# USBhub.net
KiCad netlist of a schematic drawn in Altium Designer
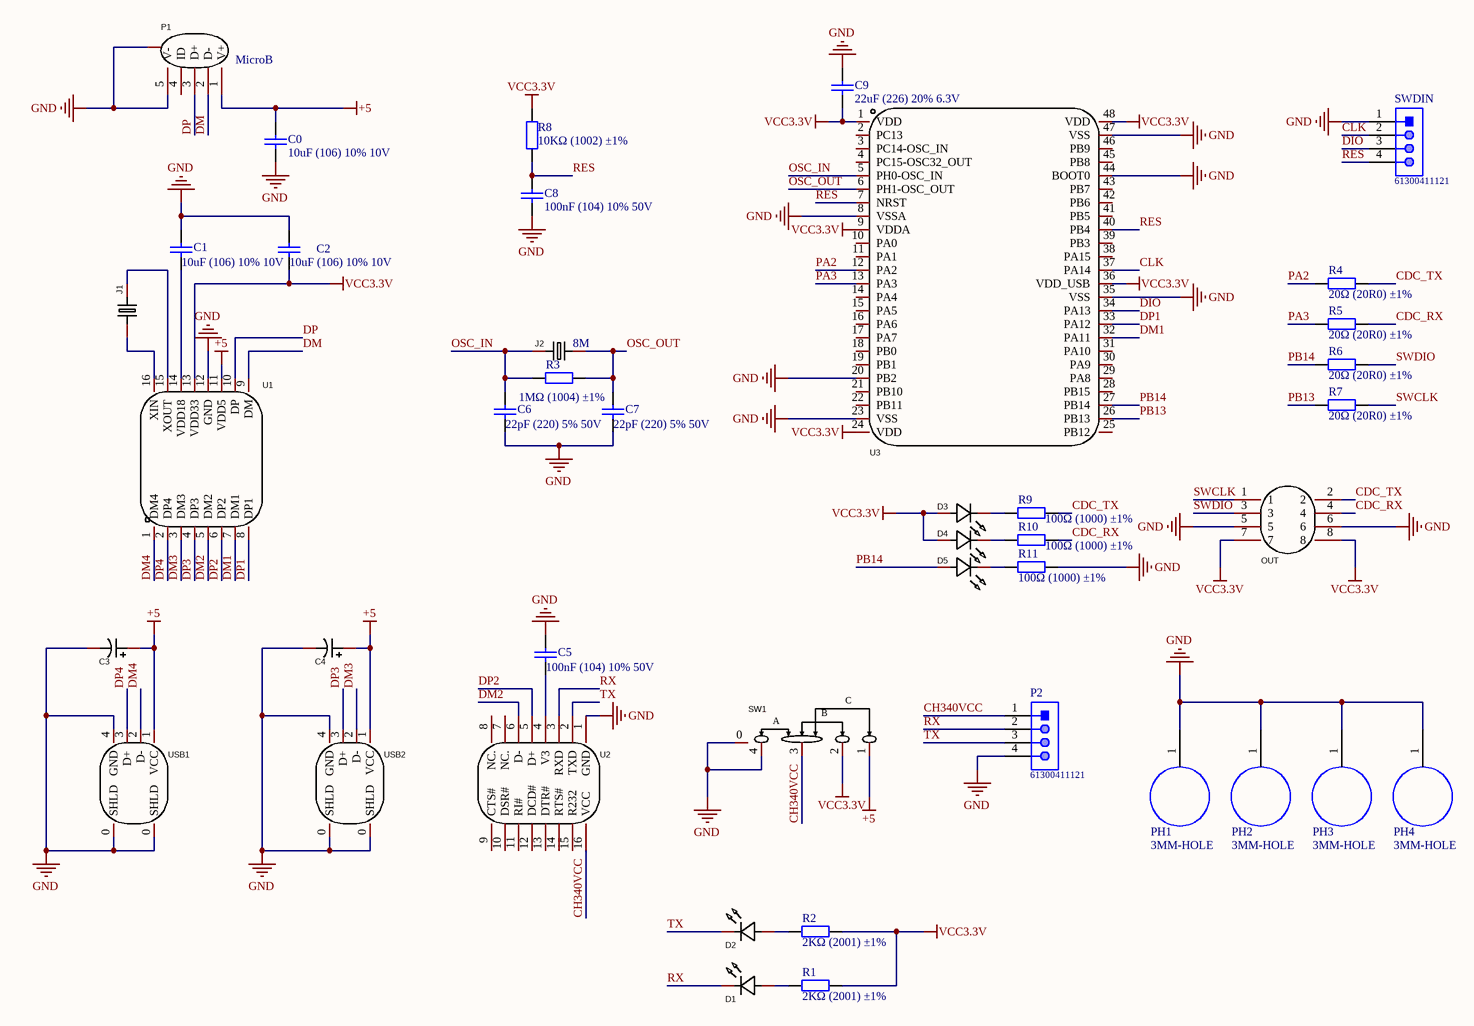
[diagram p0: USBhub.SchDoc]

(export (version "E")
  (design (tool "Eeschema 10.0.6"))
  (components
    (comp (ref "C0")
      (value "10uF (106) 10% 10V")
      (footprint "0603_C")
      (description "贴片电容")
      (libsource (lib "Cap") (part "0603 10uF (106) 10% 10V"))
    )
    (comp (ref "C1")
      (value "10uF (106) 10% 10V")
      (footprint "0603_C")
      (description "贴片电容")
      (libsource (lib "Cap") (part "0603 10uF (106) 10% 10V"))
    )
    (comp (ref "C2")
      (value "10uF (106) 10% 10V")
      (footprint "0603_C")
      (description "贴片电容")
      (libsource (lib "Cap") (part "0603 10uF (106) 10% 10V"))
    )
    (comp (ref "C3")
      (value "ULR107M1CE08TUX0CR")
      (footprint "CAP-TH_BD6.3-P2.50-D0.6-FD")
      (fields (field (name "MANUFACTURER") "MAN YUE(万裕科技)") (field (name "TOLERANCE") "±20%"))
      (libsource (lib "Stm32Basic") (part "100uF/16V"))
    )
    (comp (ref "C4")
      (value "ULR107M1CE08TUX0CR")
      (footprint "CAP-TH_BD6.3-P2.50-D0.6-FD")
      (fields (field (name "MANUFACTURER") "MAN YUE(万裕科技)") (field (name "TOLERANCE") "±20%"))
      (libsource (lib "Stm32Basic") (part "100uF/16V"))
    )
    (comp (ref "C5")
      (value "100nF (104) 10% 50V")
      (footprint "0603_C")
      (description "贴片电容")
      (libsource (lib "Cap") (part "0603 100nF (104) 10% 50V"))
    )
    (comp (ref "C6")
      (value "22pF (220) 5% 50V")
      (footprint "0603_C")
      (description "贴片电容")
      (libsource (lib "Cap") (part "0603 22pF (220) 5% 50V"))
    )
    (comp (ref "C7")
      (value "22pF (220) 5% 50V")
      (footprint "0603_C")
      (description "贴片电容")
      (libsource (lib "Cap") (part "0603 22pF (220) 5% 50V"))
    )
    (comp (ref "C8")
      (value "100nF (104) 10% 50V")
      (footprint "0603_C")
      (description "贴片电容")
      (libsource (lib "Cap") (part "0603 100nF (104) 10% 50V"))
    )
    (comp (ref "C9")
      (value "22uF (226) 20% 6.3V")
      (footprint "0603_C")
      (description "贴片电容")
      (libsource (lib "Cap") (part "0603 22uF (226) 20% 6.3V"))
    )
    (comp (ref "D1")
      (value "RF-BGB170TS-CB-E0")
      (footprint "LED0805-RD_BLUE")
      (fields (field (name "MANUFACTURER") "Refond(瑞丰)"))
      (libsource (lib "Stm32Basic") (part "RF-BGB170TS-CB-E0"))
    )
    (comp (ref "D2")
      (value "RF-BGB170TS-CB-E0")
      (footprint "LED0805-RD_BLUE")
      (fields (field (name "MANUFACTURER") "Refond(瑞丰)"))
      (libsource (lib "Stm32Basic") (part "RF-BGB170TS-CB-E0"))
    )
    (comp (ref "D3")
      (value "RF-BGB170TS-CB-E0")
      (footprint "LED0805-RD_BLUE")
      (fields (field (name "MANUFACTURER") "Refond(瑞丰)"))
      (libsource (lib "Stm32Basic") (part "RF-BGB170TS-CB-E0"))
    )
    (comp (ref "D4")
      (value "RF-BGB170TS-CB-E0")
      (footprint "LED0805-RD_BLUE")
      (fields (field (name "MANUFACTURER") "Refond(瑞丰)"))
      (libsource (lib "Stm32Basic") (part "RF-BGB170TS-CB-E0"))
    )
    (comp (ref "D5")
      (value "RF-BGB170TS-CB-E0")
      (footprint "LED0805-RD_BLUE")
      (fields (field (name "MANUFACTURER") "Refond(瑞丰)"))
      (libsource (lib "Stm32Basic") (part "RF-BGB170TS-CB-E0"))
    )
    (comp (ref "J1")
      (value "XIHCELNANF-12MHZ")
      (footprint "HC-49US_L11.5-W4.5-P4.88")
      (fields (field (name "MANUFACTURER") "TAITIEN(泰艺电子)"))
      (libsource (lib "Stm32Basic") (part "XIHCELNANF-12MHZ"))
    )
    (comp (ref "J2")
      (value "8M")
      (footprint "HC-49US_L11.5-W4.5-P4.88")
      (fields
        (field (name "MANUFACTURER") "TAITIEN(泰艺电子)")
        (field (name "MANUFACTURER PART") "XIHCELNANF-8MHZ")
      )
      (libsource (lib "Stm32Basic") (part "XIHCELNANF-8MHZ"))
    )
    (comp (ref "OUT")
      (value "A2541WV-2x4P")
      (footprint "HDR-TH_8P-P2.54-V-R2-C4-S2.54_A2541WV-2X4P")
      (fields (field (name "MANUFACTURER") "CJT(长江连接器)"))
      (libsource (lib "Stm32Basic") (part "A2541WV-2x4P"))
    )
    (comp (ref "P1")
      (value "MicroB")
      (footprint "MICRO-USB-SMD_5P-P0.65-H-F_C10418")
      (fields (field (name "MANUFACTURER") "精拓金") (field (name "MANUFACTURER PART") "920-E52A2021S10100"))
      (libsource (lib "Stm32Basic") (part "MicroB"))
    )
    (comp (ref "P2")
      (value "61300411121")
      (footprint "61300411121")
      (description "THT Vertical Pin Header WR-PHD, Pitch 2.54 mm, Single Row, 4 pins")
      (fields (field (name "MANUFACTURER") "Wurth Elektronik") (field (name "PUBLISHER") "WurthElektronik"))
      (libsource (lib "Altium Content Vault") (part "WE-CN-1P-M-R4"))
    )
    (comp (ref "PH1") (value "3MM-HOLE") (footprint "定位孔") (libsource (lib "Stm32Basic") (part "3MM-HOLE")))
    (comp (ref "PH2") (value "3MM-HOLE") (footprint "定位孔") (libsource (lib "Stm32Basic") (part "3MM-HOLE")))
    (comp (ref "PH3") (value "3MM-HOLE") (footprint "定位孔") (libsource (lib "Stm32Basic") (part "3MM-HOLE")))
    (comp (ref "PH4") (value "3MM-HOLE") (footprint "定位孔") (libsource (lib "Stm32Basic") (part "3MM-HOLE")))
    (comp (ref "R1")
      (value "2KΩ (2001) ±1%")
      (footprint "0805_R")
      (description "贴片电阻")
      (libsource (lib "RES") (part "0805 2KΩ (2001) 1%"))
    )
    (comp (ref "R2")
      (value "2KΩ (2001) ±1%")
      (footprint "0805_R")
      (description "贴片电阻")
      (libsource (lib "RES") (part "0805 2KΩ (2001) 1%"))
    )
    (comp (ref "R3")
      (value "1MΩ (1004) ±1%")
      (footprint "0805_R")
      (description "贴片电阻")
      (libsource (lib "RES") (part "0805 1MΩ (1004) 1%"))
    )
    (comp (ref "R4")
      (value "20Ω (20R0) ±1%")
      (footprint "0805_R")
      (description "贴片电阻")
      (libsource (lib "RES") (part "0805 20Ω (20R0) 1%"))
    )
    (comp (ref "R5")
      (value "20Ω (20R0) ±1%")
      (footprint "0805_R")
      (description "贴片电阻")
      (libsource (lib "RES") (part "0805 20Ω (20R0) 1%"))
    )
    (comp (ref "R6")
      (value "20Ω (20R0) ±1%")
      (footprint "0805_R")
      (description "贴片电阻")
      (libsource (lib "RES") (part "0805 20Ω (20R0) 1%"))
    )
    (comp (ref "R7")
      (value "20Ω (20R0) ±1%")
      (footprint "0805_R")
      (description "贴片电阻")
      (libsource (lib "RES") (part "0805 20Ω (20R0) 1%"))
    )
    (comp (ref "R8")
      (value "10KΩ (1002) ±1%")
      (footprint "0805_R")
      (description "贴片电阻")
      (libsource (lib "RES") (part "0805 10KΩ (1002) 1%"))
    )
    (comp (ref "R9")
      (value "100Ω (1000) ±1%")
      (footprint "0805_R")
      (description "贴片电阻")
      (libsource (lib "RES") (part "0805 100Ω (1000) 1%"))
    )
    (comp (ref "R10")
      (value "100Ω (1000) ±1%")
      (footprint "0805_R")
      (description "贴片电阻")
      (libsource (lib "RES") (part "0805 100Ω (1000) 1%"))
    )
    (comp (ref "R11")
      (value "100Ω (1000) ±1%")
      (footprint "0805_R")
      (description "贴片电阻")
      (libsource (lib "RES") (part "0805 100Ω (1000) 1%"))
    )
    (comp (ref "SW1")
      (value "TA-3506A-A1")
      (footprint "SW-SMD_4P-L12.7-W2.9-P2.00")
      (fields (field (name "MANUFACTURER") "Yuandi(台湾元迪)"))
      (libsource (lib "Stm32Basic") (part "TA-3506A-A1"))
    )
    (comp (ref "SWDIN")
      (value "61300411121")
      (footprint "61300411121")
      (description "THT Vertical Pin Header WR-PHD, Pitch 2.54 mm, Single Row, 4 pins")
      (fields (field (name "MANUFACTURER") "Wurth Elektronik") (field (name "PUBLISHER") "WurthElektronik"))
      (libsource (lib "Altium Content Vault") (part "WE-CN-1P-M-R4"))
    )
    (comp (ref "U1")
      (value "SL2.1A")
      (footprint "SOP-16_L10.0-W3.9-P1.27-LS6.0-BL")
      (fields (field (name "MANUFACTURER") "CoreChips(和芯润德)"))
      (libsource (lib "Stm32Basic") (part "SL2.1A"))
    )
    (comp (ref "U2")
      (value "CH340C")
      (footprint "SOP-16_L10.0-W3.9-P1.27-LS6.0-BL")
      (fields (field (name "MANUFACTURER") "WCH(南京沁恒)"))
      (libsource (lib "Stm32Basic") (part "CH340C"))
    )
    (comp (ref "U3")
      (value "STM32L052C8T6")
      (footprint "LQFP-48_L7.0-W7.0-P0.50-LS9.0-BL")
      (fields (field (name "MANUFACTURER") "ST(意法半导体)"))
      (libsource (lib "Stm32Basic") (part "STM32L052C8T6"))
    )
    (comp (ref "USB1")
      (value "916-352A1014Y10210")
      (footprint "USB-A-TH_USB-A-F-1")
      (fields (field (name "MANUFACTURER") "精拓金"))
      (libsource (lib "Stm32Basic") (part "916-352A1014Y10210"))
    )
    (comp (ref "USB2")
      (value "916-352A1014Y10210")
      (footprint "USB-A-TH_USB-A-F-1")
      (fields (field (name "MANUFACTURER") "精拓金"))
      (libsource (lib "Stm32Basic") (part "916-352A1014Y10210"))
    )
  )
  (nets
    (net (code "1") (name "+5") (class "Default")
      (node (ref "C0") (pin "2") (pinfunction "2_2") (pintype "passive"))
      (node (ref "C3") (pin "1") (pinfunction "1_1") (pintype "passive"))
      (node (ref "C4") (pin "1") (pinfunction "1_1") (pintype "passive"))
      (node (ref "P1") (pin "1") (pinfunction "V+_1") (pintype "passive"))
      (node (ref "SW1") (pin "1") (pinfunction "1_1") (pintype "passive"))
      (node (ref "U1") (pin "11") (pinfunction "VDD5_11") (pintype "passive"))
      (node (ref "USB1") (pin "1") (pinfunction "VCC_1") (pintype "passive"))
      (node (ref "USB2") (pin "1") (pinfunction "VCC_1") (pintype "passive"))
    )
    (net (code "2") (name "/CDC_RX") (class "Default")
      (node (ref "OUT") (pin "4") (pinfunction "4_4") (pintype "passive"))
      (node (ref "R10") (pin "2") (pinfunction "2_2") (pintype "passive"))
      (node (ref "R5") (pin "2") (pinfunction "2_2") (pintype "passive"))
    )
    (net (code "3") (name "/CDC_TX") (class "Default")
      (node (ref "OUT") (pin "2") (pinfunction "2_2") (pintype "passive"))
      (node (ref "R4") (pin "2") (pinfunction "2_2") (pintype "passive"))
      (node (ref "R9") (pin "2") (pinfunction "2_2") (pintype "passive"))
    )
    (net (code "4") (name "/CH340VCC") (class "Default")
      (node (ref "P2") (pin "1") (pinfunction "1_1") (pintype "passive"))
      (node (ref "SW1") (pin "3") (pinfunction "3_3") (pintype "passive"))
      (node (ref "U2") (pin "16") (pinfunction "VCC_16") (pintype "passive"))
    )
    (net (code "5") (name "/CLK") (class "Default")
      (node (ref "SWDIN") (pin "2") (pinfunction "2_2") (pintype "passive"))
      (node (ref "U3") (pin "37") (pinfunction "PA14_37") (pintype "passive"))
    )
    (net (code "6") (name "/DIO") (class "Default")
      (node (ref "SWDIN") (pin "3") (pinfunction "3_3") (pintype "passive"))
      (node (ref "U3") (pin "34") (pinfunction "PA13_34") (pintype "passive"))
    )
    (net (code "7") (name "/DM") (class "Default")
      (node (ref "P1") (pin "2") (pinfunction "D-_2") (pintype "passive"))
      (node (ref "U1") (pin "9") (pinfunction "DM_9") (pintype "passive"))
    )
    (net (code "8") (name "/DM1") (class "Default")
      (node (ref "U1") (pin "7") (pinfunction "DM1_7") (pintype "passive"))
      (node (ref "U3") (pin "32") (pinfunction "PA11_32") (pintype "passive"))
    )
    (net (code "9") (name "/DM2") (class "Default")
      (node (ref "U1") (pin "5") (pinfunction "DM2_5") (pintype "passive"))
      (node (ref "U2") (pin "6") (pinfunction "D-_6") (pintype "passive"))
    )
    (net (code "10") (name "/DM3") (class "Default")
      (node (ref "U1") (pin "3") (pinfunction "DM3_3") (pintype "passive"))
      (node (ref "USB2") (pin "2") (pinfunction "D-_2") (pintype "passive"))
    )
    (net (code "11") (name "/DM4") (class "Default")
      (node (ref "U1") (pin "1") (pinfunction "DM4_1") (pintype "passive"))
      (node (ref "USB1") (pin "2") (pinfunction "D-_2") (pintype "passive"))
    )
    (net (code "12") (name "/DP") (class "Default")
      (node (ref "P1") (pin "3") (pinfunction "D+_3") (pintype "passive"))
      (node (ref "U1") (pin "10") (pinfunction "DP_10") (pintype "passive"))
    )
    (net (code "13") (name "/DP1") (class "Default")
      (node (ref "U1") (pin "8") (pinfunction "DP1_8") (pintype "passive"))
      (node (ref "U3") (pin "33") (pinfunction "PA12_33") (pintype "passive"))
    )
    (net (code "14") (name "/DP2") (class "Default")
      (node (ref "U1") (pin "6") (pinfunction "DP2_6") (pintype "passive"))
      (node (ref "U2") (pin "5") (pinfunction "D+_5") (pintype "passive"))
    )
    (net (code "15") (name "/DP3") (class "Default")
      (node (ref "U1") (pin "4") (pinfunction "DP3_4") (pintype "passive"))
      (node (ref "USB2") (pin "3") (pinfunction "D+_3") (pintype "passive"))
    )
    (net (code "16") (name "/DP4") (class "Default")
      (node (ref "U1") (pin "2") (pinfunction "DP4_2") (pintype "passive"))
      (node (ref "USB1") (pin "3") (pinfunction "D+_3") (pintype "passive"))
    )
    (net (code "17") (name "/OSC_IN") (class "Default")
      (node (ref "C6") (pin "2") (pinfunction "2_2") (pintype "passive"))
      (node (ref "J2") (pin "1") (pinfunction "1_1") (pintype "passive"))
      (node (ref "R3") (pin "1") (pinfunction "1_1") (pintype "passive"))
      (node (ref "U3") (pin "5") (pinfunction "PH0-OSC_IN_5") (pintype "passive"))
    )
    (net (code "18") (name "/OSC_OUT") (class "Default")
      (node (ref "C7") (pin "2") (pinfunction "2_2") (pintype "passive"))
      (node (ref "J2") (pin "2") (pinfunction "2_2") (pintype "passive"))
      (node (ref "R3") (pin "2") (pinfunction "2_2") (pintype "passive"))
      (node (ref "U3") (pin "6") (pinfunction "PH1-OSC_OUT_6") (pintype "passive"))
    )
    (net (code "19") (name "/PA2") (class "Default")
      (node (ref "R4") (pin "1") (pinfunction "1_1") (pintype "passive"))
      (node (ref "U3") (pin "12") (pinfunction "PA2_12") (pintype "passive"))
    )
    (net (code "20") (name "/PA3") (class "Default")
      (node (ref "R5") (pin "1") (pinfunction "1_1") (pintype "passive"))
      (node (ref "U3") (pin "13") (pinfunction "PA3_13") (pintype "passive"))
    )
    (net (code "21") (name "/PB13") (class "Default")
      (node (ref "R7") (pin "1") (pinfunction "1_1") (pintype "passive"))
      (node (ref "U3") (pin "26") (pinfunction "PB13_26") (pintype "passive"))
    )
    (net (code "22") (name "/PB14") (class "Default")
      (node (ref "D5") (pin "2") (pinfunction "A_2") (pintype "passive"))
      (node (ref "R6") (pin "1") (pinfunction "1_1") (pintype "passive"))
      (node (ref "U3") (pin "27") (pinfunction "PB14_27") (pintype "passive"))
    )
    (net (code "23") (name "/RES") (class "Default")
      (node (ref "C8") (pin "2") (pinfunction "2_2") (pintype "passive"))
      (node (ref "R8") (pin "1") (pinfunction "1_1") (pintype "passive"))
      (node (ref "SWDIN") (pin "4") (pinfunction "4_4") (pintype "passive"))
      (node (ref "U3") (pin "40") (pinfunction "PB4_40") (pintype "passive"))
      (node (ref "U3") (pin "7") (pinfunction "NRST_7") (pintype "passive"))
    )
    (net (code "24") (name "/RX") (class "Default")
      (node (ref "D1") (pin "1") (pinfunction "K_1") (pintype "passive"))
      (node (ref "P2") (pin "2") (pinfunction "2_2") (pintype "passive"))
      (node (ref "U2") (pin "3") (pinfunction "RXD_3") (pintype "passive"))
    )
    (net (code "25") (name "/SWCLK") (class "Default")
      (node (ref "OUT") (pin "1") (pinfunction "1_1") (pintype "passive"))
      (node (ref "R7") (pin "2") (pinfunction "2_2") (pintype "passive"))
    )
    (net (code "26") (name "/SWDIO") (class "Default")
      (node (ref "OUT") (pin "3") (pinfunction "3_3") (pintype "passive"))
      (node (ref "R6") (pin "2") (pinfunction "2_2") (pintype "passive"))
    )
    (net (code "27") (name "/TX") (class "Default")
      (node (ref "D2") (pin "1") (pinfunction "K_1") (pintype "passive"))
      (node (ref "P2") (pin "3") (pinfunction "3_3") (pintype "passive"))
      (node (ref "U2") (pin "2") (pinfunction "TXD_2") (pintype "passive"))
    )
    (net (code "28") (name "GND") (class "Default")
      (node (ref "C0") (pin "1") (pinfunction "1_1") (pintype "passive"))
      (node (ref "C1") (pin "2") (pinfunction "2_2") (pintype "passive"))
      (node (ref "C2") (pin "2") (pinfunction "2_2") (pintype "passive"))
      (node (ref "C3") (pin "2") (pinfunction "2_2") (pintype "passive"))
      (node (ref "C4") (pin "2") (pinfunction "2_2") (pintype "passive"))
      (node (ref "C5") (pin "2") (pinfunction "2_2") (pintype "passive"))
      (node (ref "C6") (pin "1") (pinfunction "1_1") (pintype "passive"))
      (node (ref "C7") (pin "1") (pinfunction "1_1") (pintype "passive"))
      (node (ref "C8") (pin "1") (pinfunction "1_1") (pintype "passive"))
      (node (ref "C9") (pin "2") (pinfunction "2_2") (pintype "passive"))
      (node (ref "OUT") (pin "5") (pinfunction "5_5") (pintype "passive"))
      (node (ref "OUT") (pin "6") (pinfunction "6_6") (pintype "passive"))
      (node (ref "P1") (pin "0") (pinfunction "MTN_0") (pintype "passive"))
      (node (ref "P1") (pin "5") (pinfunction "V-_5") (pintype "passive"))
      (node (ref "P2") (pin "4") (pinfunction "4_4") (pintype "passive"))
      (node (ref "PH1") (pin "1") (pinfunction "1_1") (pintype "passive"))
      (node (ref "PH2") (pin "1") (pinfunction "1_1") (pintype "passive"))
      (node (ref "PH3") (pin "1") (pinfunction "1_1") (pintype "passive"))
      (node (ref "PH4") (pin "1") (pinfunction "1_1") (pintype "passive"))
      (node (ref "R11") (pin "2") (pinfunction "2_2") (pintype "passive"))
      (node (ref "SW1") (pin "0") (pinfunction "0_0") (pintype "passive"))
      (node (ref "SW1") (pin "4") (pinfunction "4_4") (pintype "passive"))
      (node (ref "SWDIN") (pin "1") (pinfunction "1_1") (pintype "passive"))
      (node (ref "U1") (pin "12") (pinfunction "GND_12") (pintype "passive"))
      (node (ref "U2") (pin "1") (pinfunction "GND_1") (pintype "passive"))
      (node (ref "U3") (pin "20") (pinfunction "PB2_20") (pintype "passive"))
      (node (ref "U3") (pin "23") (pinfunction "VSS_23") (pintype "passive"))
      (node (ref "U3") (pin "35") (pinfunction "VSS_35") (pintype "passive"))
      (node (ref "U3") (pin "44") (pinfunction "BOOT0_44") (pintype "passive"))
      (node (ref "U3") (pin "47") (pinfunction "VSS_47") (pintype "passive"))
      (node (ref "U3") (pin "8") (pinfunction "VSSA_8") (pintype "passive"))
      (node (ref "USB1") (pin "0") (pinfunction "SHLD_0") (pintype "passive"))
      (node (ref "USB1") (pin "4") (pinfunction "GND_4") (pintype "passive"))
      (node (ref "USB2") (pin "0") (pinfunction "SHLD_0") (pintype "passive"))
      (node (ref "USB2") (pin "4") (pinfunction "GND_4") (pintype "passive"))
    )
    (net (code "29") (name "Net-(D1-A)") (class "Default")
      (node (ref "D1") (pin "2") (pinfunction "A_2") (pintype "passive"))
      (node (ref "R1") (pin "1") (pinfunction "1_1") (pintype "passive"))
    )
    (net (code "30") (name "Net-(D2-A)") (class "Default")
      (node (ref "D2") (pin "2") (pinfunction "A_2") (pintype "passive"))
      (node (ref "R2") (pin "1") (pinfunction "1_1") (pintype "passive"))
    )
    (net (code "31") (name "Net-(D3-K)") (class "Default")
      (node (ref "D3") (pin "1") (pinfunction "K_1") (pintype "passive"))
      (node (ref "R9") (pin "1") (pinfunction "1_1") (pintype "passive"))
    )
    (net (code "32") (name "Net-(D4-K)") (class "Default")
      (node (ref "D4") (pin "1") (pinfunction "K_1") (pintype "passive"))
      (node (ref "R10") (pin "1") (pinfunction "1_1") (pintype "passive"))
    )
    (net (code "33") (name "Net-(D5-K)") (class "Default")
      (node (ref "D5") (pin "1") (pinfunction "K_1") (pintype "passive"))
      (node (ref "R11") (pin "1") (pinfunction "1_1") (pintype "passive"))
    )
    (net (code "34") (name "Net-(U1-VDD18)") (class "Default")
      (node (ref "C1") (pin "1") (pinfunction "1_1") (pintype "passive"))
      (node (ref "U1") (pin "14") (pinfunction "VDD18_14") (pintype "passive"))
    )
    (net (code "35") (name "Net-(U1-XIN)") (class "Default")
      (node (ref "J1") (pin "1") (pinfunction "1_1") (pintype "passive"))
      (node (ref "U1") (pin "16") (pinfunction "XIN_16") (pintype "passive"))
    )
    (net (code "36") (name "Net-(U1-XOUT)") (class "Default")
      (node (ref "J1") (pin "2") (pinfunction "2_2") (pintype "passive"))
      (node (ref "U1") (pin "15") (pinfunction "XOUT_15") (pintype "passive"))
    )
    (net (code "37") (name "Net-(U2-V3)") (class "Default")
      (node (ref "C5") (pin "1") (pinfunction "1_1") (pintype "passive"))
      (node (ref "U2") (pin "4") (pinfunction "V3_4") (pintype "passive"))
    )
    (net (code "38") (name "VCC3.3V") (class "Default")
      (node (ref "C2") (pin "1") (pinfunction "1_1") (pintype "passive"))
      (node (ref "C9") (pin "1") (pinfunction "1_1") (pintype "passive"))
      (node (ref "D3") (pin "2") (pinfunction "A_2") (pintype "passive"))
      (node (ref "D4") (pin "2") (pinfunction "A_2") (pintype "passive"))
      (node (ref "OUT") (pin "7") (pinfunction "7_7") (pintype "passive"))
      (node (ref "OUT") (pin "8") (pinfunction "8_8") (pintype "passive"))
      (node (ref "R1") (pin "2") (pinfunction "2_2") (pintype "passive"))
      (node (ref "R2") (pin "2") (pinfunction "2_2") (pintype "passive"))
      (node (ref "R8") (pin "2") (pinfunction "2_2") (pintype "passive"))
      (node (ref "SW1") (pin "2") (pinfunction "2_2") (pintype "passive"))
      (node (ref "U1") (pin "13") (pinfunction "VDD33_13") (pintype "passive"))
      (node (ref "U3") (pin "1") (pinfunction "VDD_1") (pintype "passive"))
      (node (ref "U3") (pin "24") (pinfunction "VDD_24") (pintype "passive"))
      (node (ref "U3") (pin "36") (pinfunction "VDD_USB_36") (pintype "passive"))
      (node (ref "U3") (pin "48") (pinfunction "VDD_48") (pintype "passive"))
      (node (ref "U3") (pin "9") (pinfunction "VDDA_9") (pintype "passive"))
    )
    (net (code "39") (name "unconnected-(P1-ID-Pad4)") (class "Default")
      (node (ref "P1") (pin "4") (pinfunction "ID_4") (pintype "passive"))
    )
    (net (code "40") (name "unconnected-(U2-CTS#-Pad9)") (class "Default")
      (node (ref "U2") (pin "9") (pinfunction "CTS#_9") (pintype "passive"))
    )
    (net (code "41") (name "unconnected-(U2-DCD#-Pad12)") (class "Default")
      (node (ref "U2") (pin "12") (pinfunction "DCD#_12") (pintype "passive"))
    )
    (net (code "42") (name "unconnected-(U2-DSR#-Pad10)") (class "Default")
      (node (ref "U2") (pin "10") (pinfunction "DSR#_10") (pintype "passive"))
    )
    (net (code "43") (name "unconnected-(U2-DTR#-Pad13)") (class "Default")
      (node (ref "U2") (pin "13") (pinfunction "DTR#_13") (pintype "passive"))
    )
    (net (code "44") (name "unconnected-(U2-NC.-Pad7)") (class "Default")
      (node (ref "U2") (pin "7") (pinfunction "NC._7") (pintype "passive"))
    )
    (net (code "45") (name "unconnected-(U2-NC.-Pad8)") (class "Default")
      (node (ref "U2") (pin "8") (pinfunction "NC._8") (pintype "passive"))
    )
    (net (code "46") (name "unconnected-(U2-R232-Pad15)") (class "Default")
      (node (ref "U2") (pin "15") (pinfunction "R232_15") (pintype "passive"))
    )
    (net (code "47") (name "unconnected-(U2-RI#-Pad11)") (class "Default")
      (node (ref "U2") (pin "11") (pinfunction "RI#_11") (pintype "passive"))
    )
    (net (code "48") (name "unconnected-(U2-RTS#-Pad14)") (class "Default")
      (node (ref "U2") (pin "14") (pinfunction "RTS#_14") (pintype "passive"))
    )
    (net (code "49") (name "unconnected-(U3-PA0-Pad10)") (class "Default")
      (node (ref "U3") (pin "10") (pinfunction "PA0_10") (pintype "passive"))
    )
    (net (code "50") (name "unconnected-(U3-PA1-Pad11)") (class "Default")
      (node (ref "U3") (pin "11") (pinfunction "PA1_11") (pintype "passive"))
    )
    (net (code "51") (name "unconnected-(U3-PA4-Pad14)") (class "Default")
      (node (ref "U3") (pin "14") (pinfunction "PA4_14") (pintype "passive"))
    )
    (net (code "52") (name "unconnected-(U3-PA5-Pad15)") (class "Default")
      (node (ref "U3") (pin "15") (pinfunction "PA5_15") (pintype "passive"))
    )
    (net (code "53") (name "unconnected-(U3-PA6-Pad16)") (class "Default")
      (node (ref "U3") (pin "16") (pinfunction "PA6_16") (pintype "passive"))
    )
    (net (code "54") (name "unconnected-(U3-PA7-Pad17)") (class "Default")
      (node (ref "U3") (pin "17") (pinfunction "PA7_17") (pintype "passive"))
    )
    (net (code "55") (name "unconnected-(U3-PA8-Pad29)") (class "Default")
      (node (ref "U3") (pin "29") (pinfunction "PA8_29") (pintype "passive"))
    )
    (net (code "56") (name "unconnected-(U3-PA9-Pad30)") (class "Default")
      (node (ref "U3") (pin "30") (pinfunction "PA9_30") (pintype "passive"))
    )
    (net (code "57") (name "unconnected-(U3-PA10-Pad31)") (class "Default")
      (node (ref "U3") (pin "31") (pinfunction "PA10_31") (pintype "passive"))
    )
    (net (code "58") (name "unconnected-(U3-PA15-Pad38)") (class "Default")
      (node (ref "U3") (pin "38") (pinfunction "PA15_38") (pintype "passive"))
    )
    (net (code "59") (name "unconnected-(U3-PB0-Pad18)") (class "Default")
      (node (ref "U3") (pin "18") (pinfunction "PB0_18") (pintype "passive"))
    )
    (net (code "60") (name "unconnected-(U3-PB1-Pad19)") (class "Default")
      (node (ref "U3") (pin "19") (pinfunction "PB1_19") (pintype "passive"))
    )
    (net (code "61") (name "unconnected-(U3-PB3-Pad39)") (class "Default")
      (node (ref "U3") (pin "39") (pinfunction "PB3_39") (pintype "passive"))
    )
    (net (code "62") (name "unconnected-(U3-PB5-Pad41)") (class "Default")
      (node (ref "U3") (pin "41") (pinfunction "PB5_41") (pintype "passive"))
    )
    (net (code "63") (name "unconnected-(U3-PB6-Pad42)") (class "Default")
      (node (ref "U3") (pin "42") (pinfunction "PB6_42") (pintype "passive"))
    )
    (net (code "64") (name "unconnected-(U3-PB7-Pad43)") (class "Default")
      (node (ref "U3") (pin "43") (pinfunction "PB7_43") (pintype "passive"))
    )
    (net (code "65") (name "unconnected-(U3-PB8-Pad45)") (class "Default")
      (node (ref "U3") (pin "45") (pinfunction "PB8_45") (pintype "passive"))
    )
    (net (code "66") (name "unconnected-(U3-PB9-Pad46)") (class "Default")
      (node (ref "U3") (pin "46") (pinfunction "PB9_46") (pintype "passive"))
    )
    (net (code "67") (name "unconnected-(U3-PB10-Pad21)") (class "Default")
      (node (ref "U3") (pin "21") (pinfunction "PB10_21") (pintype "passive"))
    )
    (net (code "68") (name "unconnected-(U3-PB11-Pad22)") (class "Default")
      (node (ref "U3") (pin "22") (pinfunction "PB11_22") (pintype "passive"))
    )
    (net (code "69") (name "unconnected-(U3-PB12-Pad25)") (class "Default")
      (node (ref "U3") (pin "25") (pinfunction "PB12_25") (pintype "passive"))
    )
    (net (code "70") (name "unconnected-(U3-PB15-Pad28)") (class "Default")
      (node (ref "U3") (pin "28") (pinfunction "PB15_28") (pintype "passive"))
    )
    (net (code "71") (name "unconnected-(U3-PC13-Pad2)") (class "Default")
      (node (ref "U3") (pin "2") (pinfunction "PC13_2") (pintype "passive"))
    )
    (net (code "72") (name "unconnected-(U3-PC14-OSC_IN-Pad3)") (class "Default")
      (node (ref "U3") (pin "3") (pinfunction "PC14-OSC_IN_3") (pintype "passive"))
    )
    (net (code "73") (name "unconnected-(U3-PC15-OSC32_OUT-Pad4)") (class "Default")
      (node (ref "U3") (pin "4") (pinfunction "PC15-OSC32_OUT_4") (pintype "passive"))
    )
  )
)
